# switch-acdetect.net
KiCad netlist of a schematic drawn in Altium Designer
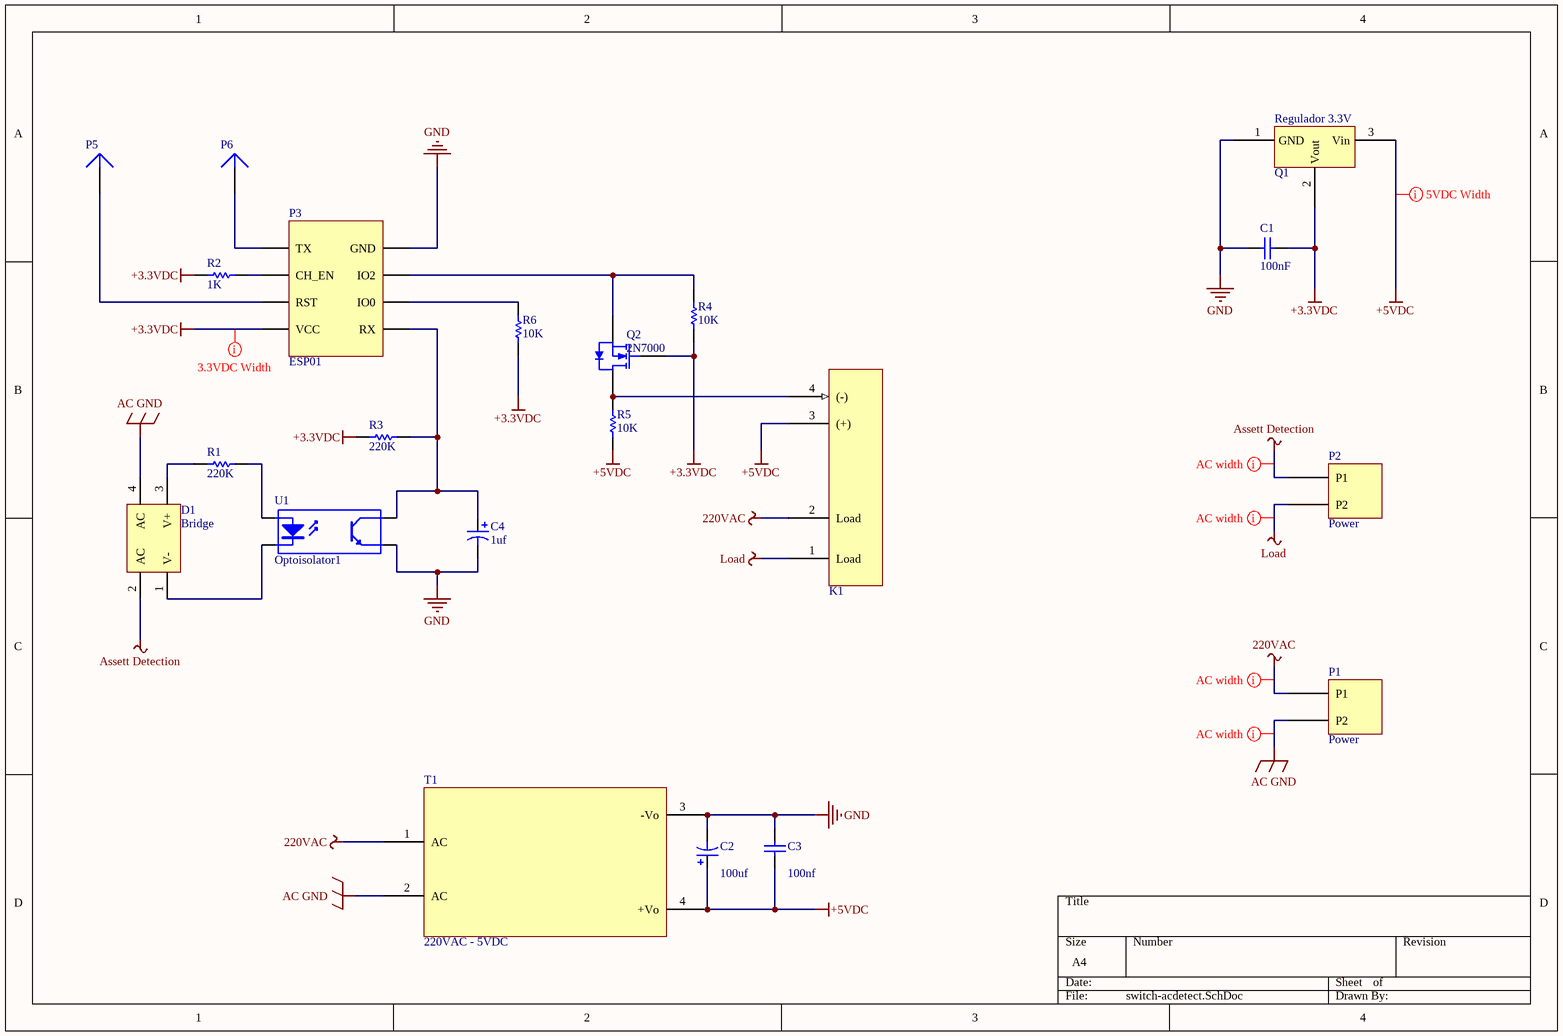
[diagram p0: switch-acdetect.SchDoc]

(export (version "E")
  (design (tool "Eeschema 10.0.6"))
  (components
    (comp (ref "C1")
      (value "100nF")
      (footprint "RAD-0.1")
      (description "Capacitor")
      (fields (field (name "Comment") "100nf") (field (name "PUBLISHER") "Altium Limited"))
      (libsource (lib "Miscellaneous Devices") (part "Cap"))
    )
    (comp (ref "C2")
      (value "100uf")
      (footprint "RAD-0.1")
      (description "Polarized Capacitor (Radial)")
      (fields (field (name "Comment") "Cap Pol1") (field (name "PUBLISHER") "Altium Limited"))
      (libsource (lib "Miscellaneous Devices") (part "Cap Pol1"))
    )
    (comp (ref "C3")
      (value "100nf")
      (footprint "RAD-0.1")
      (description "Capacitor")
      (fields (field (name "Comment") "Cap") (field (name "PUBLISHER") "Altium Limited"))
      (libsource (lib "Miscellaneous Devices") (part "Cap"))
    )
    (comp (ref "C4")
      (value "1uf")
      (footprint "RAD-0.1")
      (description "Polarized Capacitor (Radial)")
      (fields (field (name "Comment") "Cap Pol1") (field (name "PUBLISHER") "Altium Limited"))
      (libsource (lib "Miscellaneous Devices") (part "Cap Pol1"))
    )
    (comp (ref "D1")
      (value "Bridge")
      (footprint "DB157")
      (description "Diode Bridge")
      (fields (field (name "PUBLISHER") "Altium Limited"))
      (libsource (lib "Miscellaneous Devices") (part "Bridge2"))
    )
    (comp (ref "K1")
      (value "G3MB-202P DC5")
      (footprint "G3MB-202P DC5")
      (description "RELAY MINI SSR 240VAC@2A ZERO")
      (fields (field (name "MFR") "Omron"))
      (libsource (lib "G3MB-202P") (part "G3MB-202P DC5"))
    )
    (comp (ref "P1")
      (value "Power")
      (footprint "ScrewTerminal-X2")
      (libsource (lib "ScrewTerminal_2X") (part "ScrewTerminal"))
    )
    (comp (ref "P2")
      (value "Power")
      (footprint "ScrewTerminal-X2")
      (libsource (lib "ScrewTerminal_2X") (part "ScrewTerminal"))
    )
    (comp (ref "P3") (value "ESP01") (footprint "HDR2X4") (libsource (lib "ESP01") (part "ESP01")))
    (comp (ref "P5")
      (value "Plug")
      (footprint "PIN1")
      (fields (field (name "PUBLISHER") "Altium Limited"))
      (libsource (lib "Miscellaneous Connectors") (part "Plug"))
    )
    (comp (ref "P6")
      (value "Plug")
      (footprint "PIN1")
      (fields (field (name "PUBLISHER") "Altium Limited"))
      (libsource (lib "Miscellaneous Connectors") (part "Plug"))
    )
    (comp (ref "Q1")
      (value "Regulador 3.3V")
      (footprint "TO-220-AB")
      (libsource (lib "AMS1117") (part "AMS1117"))
    )
    (comp (ref "Q2")
      (value "2N7000")
      (footprint "Miscellaneous Devices:TO-92")
      (description "N-channel Enhancement Mode Field-effect Transistor")
      (fields (field (name "PUBLISHER") "Altium Limited"))
      (libsource (lib "Philips Discrete MOSFET - Low Power") (part "2N7000"))
    )
    (comp (ref "R1")
      (value "220K")
      (footprint "AXIAL-0.3")
      (description "Resistor")
      (fields (field (name "Comment") "10K") (field (name "PUBLISHER") "Altium Limited"))
      (libsource (lib "Miscellaneous Devices") (part "Res1"))
    )
    (comp (ref "R2")
      (value "1K")
      (footprint "AXIAL-0.3")
      (description "Resistor")
      (fields (field (name "Comment") "10K") (field (name "PUBLISHER") "Altium Limited"))
      (libsource (lib "Miscellaneous Devices") (part "Res1"))
    )
    (comp (ref "R3")
      (value "220K")
      (footprint "AXIAL-0.3")
      (description "Resistor")
      (fields (field (name "Comment") "10K") (field (name "PUBLISHER") "Altium Limited"))
      (libsource (lib "Miscellaneous Devices") (part "Res1"))
    )
    (comp (ref "R4")
      (value "10K")
      (footprint "AXIAL-0.3")
      (description "Resistor")
      (fields (field (name "PUBLISHER") "Altium Limited"))
      (libsource (lib "Miscellaneous Devices") (part "Res1"))
    )
    (comp (ref "R5")
      (value "10K")
      (footprint "AXIAL-0.3")
      (description "Resistor")
      (fields (field (name "PUBLISHER") "Altium Limited"))
      (libsource (lib "Miscellaneous Devices") (part "Res1"))
    )
    (comp (ref "R6")
      (value "10K")
      (footprint "AXIAL-0.3")
      (description "Resistor")
      (fields (field (name "PUBLISHER") "Altium Limited"))
      (libsource (lib "Miscellaneous Devices") (part "Res1"))
    )
    (comp (ref "T1")
      (value "220VAC - 5VDC")
      (footprint "HLK-PM")
      (description "HLK-PM*")
      (fields (field (name "MFR") "HLK-PM01"))
      (libsource (lib "HLK-PM") (part "HLK-PM"))
    )
    (comp (ref "U1")
      (value "Optoisolator1")
      (footprint "DIP-4")
      (description "4-Pin Phototransistor Optocoupler")
      (fields (field (name "PUBLISHER") "Altium Limited"))
      (libsource (lib "Miscellaneous Devices") (part "Optoisolator1"))
    )
  )
  (nets
    (net (code "1") (name "+3.3VDC") (class "Default")
      (node (ref "C1") (pin "2") (pinfunction "2_2") (pintype "passive"))
      (node (ref "P3") (pin "4") (pinfunction "VCC_4") (pintype "passive"))
      (node (ref "Q1") (pin "2") (pinfunction "Vout_2") (pintype "passive"))
      (node (ref "Q2") (pin "2") (pinfunction "G_2") (pintype "passive"))
      (node (ref "R2") (pin "1") (pinfunction "1_1") (pintype "passive"))
      (node (ref "R3") (pin "1") (pinfunction "1_1") (pintype "passive"))
      (node (ref "R4") (pin "2") (pinfunction "2_2") (pintype "passive"))
      (node (ref "R6") (pin "1") (pinfunction "1_1") (pintype "passive"))
    )
    (net (code "2") (name "+5VDC") (class "Default")
      (node (ref "C2") (pin "1") (pinfunction "1_1") (pintype "passive"))
      (node (ref "C3") (pin "1") (pinfunction "1_1") (pintype "passive"))
      (node (ref "K1") (pin "3") (pinfunction "(+)_3") (pintype "power_in"))
      (node (ref "Q1") (pin "3") (pinfunction "Vin_3") (pintype "passive"))
      (node (ref "R5") (pin "2") (pinfunction "2_2") (pintype "passive"))
      (node (ref "T1") (pin "4") (pinfunction "+Vo_4") (pintype "passive"))
    )
    (net (code "3") (name "220VAC") (class "Default")
      (node (ref "K1") (pin "2") (pinfunction "Load_2") (pintype "passive"))
      (node (ref "P1") (pin "1") (pinfunction "P1_1") (pintype "passive"))
      (node (ref "T1") (pin "1") (pinfunction "AC_1") (pintype "power_in"))
    )
    (net (code "4") (name "AC GND") (class "Default")
      (node (ref "D1") (pin "4") (pinfunction "AC_4") (pintype "passive"))
      (node (ref "P1") (pin "2") (pinfunction "P2_2") (pintype "passive"))
      (node (ref "T1") (pin "2") (pinfunction "AC_2") (pintype "power_in"))
    )
    (net (code "5") (name "Assett Detection") (class "Default")
      (node (ref "D1") (pin "2") (pinfunction "AC_2") (pintype "passive"))
      (node (ref "P2") (pin "1") (pinfunction "P1_1") (pintype "passive"))
    )
    (net (code "6") (name "GND") (class "Default")
      (node (ref "C1") (pin "1") (pinfunction "1_1") (pintype "passive"))
      (node (ref "C2") (pin "2") (pinfunction "2_2") (pintype "passive"))
      (node (ref "C3") (pin "2") (pinfunction "2_2") (pintype "passive"))
      (node (ref "C4") (pin "2") (pinfunction "2_2") (pintype "passive"))
      (node (ref "P3") (pin "5") (pinfunction "GND_5") (pintype "passive"))
      (node (ref "Q1") (pin "1") (pinfunction "GND_1") (pintype "passive"))
      (node (ref "T1") (pin "3") (pinfunction "-Vo_3") (pintype "passive"))
      (node (ref "U1") (pin "3") (pinfunction "E_3") (pintype "passive"))
    )
    (net (code "7") (name "Load") (class "Default")
      (node (ref "K1") (pin "1") (pinfunction "Load_1") (pintype "passive"))
      (node (ref "P2") (pin "2") (pinfunction "P2_2") (pintype "passive"))
    )
    (net (code "8") (name "Net-(D1-V+)") (class "Default")
      (node (ref "D1") (pin "3") (pinfunction "V+_3") (pintype "passive"))
      (node (ref "R1") (pin "1") (pinfunction "1_1") (pintype "passive"))
    )
    (net (code "9") (name "Net-(D1-V-)") (class "Default")
      (node (ref "D1") (pin "1") (pinfunction "V-_1") (pintype "passive"))
      (node (ref "U1") (pin "2") (pinfunction "K_2") (pintype "passive"))
    )
    (net (code "10") (name "Net-(K1-(-))") (class "Default")
      (node (ref "K1") (pin "4") (pinfunction "(-)_4") (pintype "input"))
      (node (ref "Q2") (pin "1") (pinfunction "D_1") (pintype "passive"))
      (node (ref "R5") (pin "1") (pinfunction "1_1") (pintype "passive"))
    )
    (net (code "11") (name "Net-(P3-CH_EN)") (class "Default")
      (node (ref "P3") (pin "2") (pinfunction "CH_EN_2") (pintype "passive"))
      (node (ref "R2") (pin "2") (pinfunction "2_2") (pintype "passive"))
    )
    (net (code "12") (name "Net-(P3-IO0)") (class "Default")
      (node (ref "P3") (pin "7") (pinfunction "IO0_7") (pintype "passive"))
      (node (ref "R6") (pin "2") (pinfunction "2_2") (pintype "passive"))
    )
    (net (code "13") (name "Net-(P3-IO2)") (class "Default")
      (node (ref "P3") (pin "6") (pinfunction "IO2_6") (pintype "passive"))
      (node (ref "Q2") (pin "3") (pinfunction "S_3") (pintype "passive"))
      (node (ref "R4") (pin "1") (pinfunction "1_1") (pintype "passive"))
    )
    (net (code "14") (name "Net-(P3-RST)") (class "Default")
      (node (ref "P3") (pin "3") (pinfunction "RST_3") (pintype "passive"))
      (node (ref "P5") (pin "1") (pinfunction "1_1") (pintype "passive"))
    )
    (net (code "15") (name "Net-(P3-RX)") (class "Default")
      (node (ref "C4") (pin "1") (pinfunction "1_1") (pintype "passive"))
      (node (ref "P3") (pin "8") (pinfunction "RX_8") (pintype "passive"))
      (node (ref "R3") (pin "2") (pinfunction "2_2") (pintype "passive"))
      (node (ref "U1") (pin "4") (pinfunction "C_4") (pintype "passive"))
    )
    (net (code "16") (name "Net-(P3-TX)") (class "Default")
      (node (ref "P3") (pin "1") (pinfunction "TX_1") (pintype "passive"))
      (node (ref "P6") (pin "1") (pinfunction "1_1") (pintype "passive"))
    )
    (net (code "17") (name "Net-(U1-A)") (class "Default")
      (node (ref "R1") (pin "2") (pinfunction "2_2") (pintype "passive"))
      (node (ref "U1") (pin "1") (pinfunction "A_1") (pintype "passive"))
    )
  )
)
